# MicrobitQwiic_138.net
KiCad netlist of a schematic drawn in Altium Designer
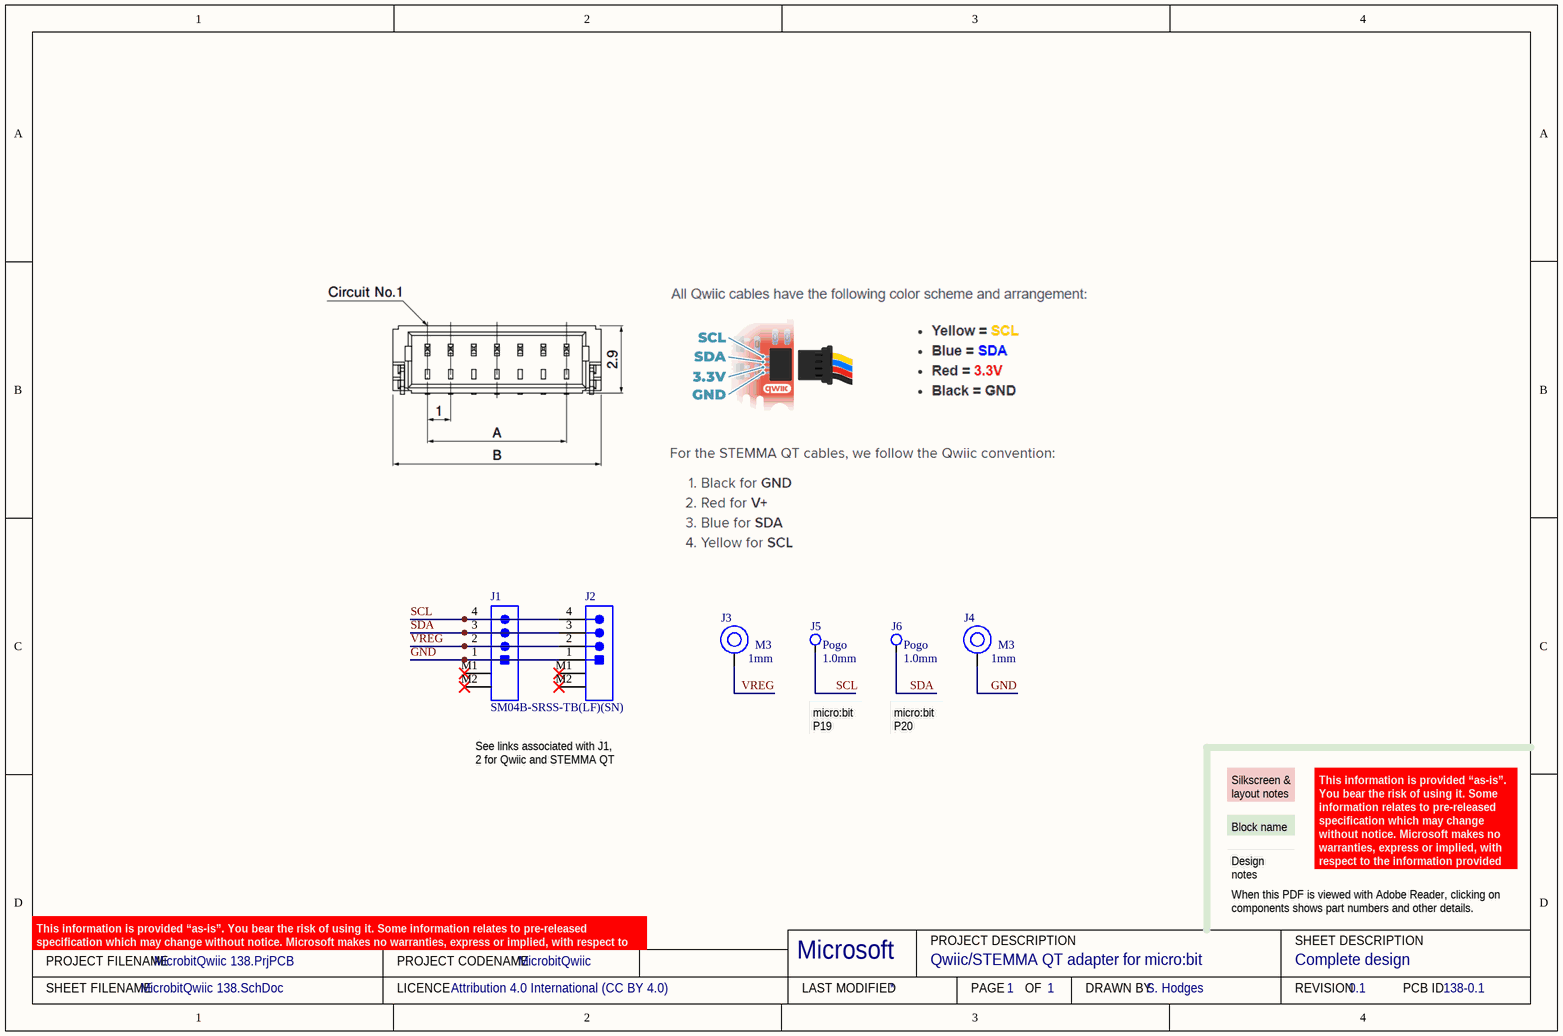
[diagram p0: MicrobitQwiic 138.SchDoc]

(export (version "E")
  (design (tool "Eeschema 10.0.6"))
  (components
    (comp (ref "J1")
      (value "SM04B-SRSS-TB(LF)(SN)")
      (footprint "SM04B-SRSS-TB(LF)(SN):SM04B-SRSS-TB(LF)(SN)")
      (description "CONN HEADER SMD R/A 4POS 1MM")
      (fields
        (field (name "MANUFACTURER") "JST")
        (field (name "MANUFACTURER PART NUMBER") "SM04B-SRSS-TB(LF)(SN)")
      )
      (libsource (lib "JST") (part "SM04B-SRSS-TB(LF)(SN)"))
    )
    (comp (ref "J2")
      (value "SM04B-SRSS-TB(LF)(SN)")
      (footprint "SM04B-SRSS-TB(LF)(SN):SM04B-SRSS-TB(LF)(SN)")
      (description "CONN HEADER SMD R/A 4POS 1MM")
      (fields (field (name "MANUFACTURER") "JST"))
      (libsource (lib "JST") (part "SM04B-SRSS-TB(LF)(SN)"))
    )
    (comp (ref "J3")
      (value "SMTSO-M3-1mm")
      (footprint "generic-smtso:smtso M3x1mm")
      (fields (field (name "STANDOFF HEIGHT") "1mm") (field (name "DIAMETER") "M3"))
      (libsource (lib "generic-smtso") (part "SMTSO-M3-1mm"))
    )
    (comp (ref "J4")
      (value "SMTSO-M3-1mm")
      (footprint "generic-smtso:smtso M3x1mm")
      (fields (field (name "STANDOFF HEIGHT") "1mm") (field (name "DIAMETER") "M3"))
      (libsource (lib "generic-smtso") (part "SMTSO-M3-1mm"))
    )
    (comp (ref "J5")
      (value "Pogo")
      (footprint "ALPS-SCTA2A0100:ALPS-SCTA2A0100")
      (description "PCB 3A Spring contct SMT 1.4x1.4x1.2mm, working height 0.8-1.2mm")
      (fields
        (field (name "MANUFACTURER") "Alps Electric")
        (field (name "MANUFACTURER PART NUMBER") "SCTA2A0100")
        (field (name "WORKING HEIGHT") "1.0mm")
      )
      (libsource (lib "Alps") (part "SCTA2A0100"))
    )
    (comp (ref "J6")
      (value "Pogo")
      (footprint "ALPS-SCTA2A0100:ALPS-SCTA2A0100")
      (description "PCB 3A Spring contct SMT 1.4x1.4x1.2mm, working height 0.8-1.2mm")
      (fields
        (field (name "MANUFACTURER") "Alps Electric")
        (field (name "MANUFACTURER PART NUMBER") "SCTA2A0100")
        (field (name "WORKING HEIGHT") "1.0mm")
      )
      (libsource (lib "Alps") (part "SCTA2A0100"))
    )
  )
  (nets
    (net (code "1") (name "/GND") (class "Default")
      (node (ref "J1") (pin "1") (pinfunction "GND_1") (pintype "passive"))
      (node (ref "J2") (pin "1") (pinfunction "GND_1") (pintype "passive"))
      (node (ref "J4") (pin "1") (pinfunction "1_1") (pintype "passive"))
    )
    (net (code "2") (name "/SCL") (class "Default")
      (node (ref "J1") (pin "4") (pinfunction "SCL_4") (pintype "passive"))
      (node (ref "J2") (pin "4") (pinfunction "SCL_4") (pintype "passive"))
      (node (ref "J5") (pin "1") (pinfunction "1_1") (pintype "passive"))
    )
    (net (code "3") (name "/SDA") (class "Default")
      (node (ref "J1") (pin "3") (pinfunction "SDA_3") (pintype "passive"))
      (node (ref "J2") (pin "3") (pinfunction "SDA_3") (pintype "passive"))
      (node (ref "J6") (pin "1") (pinfunction "1_1") (pintype "passive"))
    )
    (net (code "4") (name "/VREG") (class "Default")
      (node (ref "J1") (pin "2") (pinfunction "VCC_2") (pintype "passive"))
      (node (ref "J2") (pin "2") (pinfunction "VCC_2") (pintype "passive"))
      (node (ref "J3") (pin "1") (pinfunction "1_1") (pintype "passive"))
    )
    (net (code "5") (name "unconnected-(J1-PadM1)") (class "Default")
      (node (ref "J1") (pin "M1") (pinfunction "M1_M1") (pintype "passive+no_connect"))
    )
    (net (code "6") (name "unconnected-(J1-PadM2)") (class "Default")
      (node (ref "J1") (pin "M2") (pinfunction "M2_M2") (pintype "passive+no_connect"))
    )
    (net (code "7") (name "unconnected-(J2-PadM1)") (class "Default")
      (node (ref "J2") (pin "M1") (pinfunction "M1_M1") (pintype "passive+no_connect"))
    )
    (net (code "8") (name "unconnected-(J2-PadM2)") (class "Default")
      (node (ref "J2") (pin "M2") (pinfunction "M2_M2") (pintype "passive+no_connect"))
    )
  )
)
